# MCUReset.net
KiCad netlist of a schematic drawn in Altium Designer
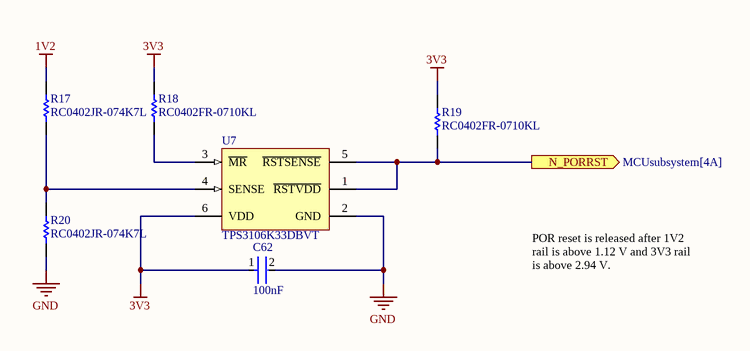
[diagram p0: MCUReset.SchDoc]

(export (version "E")
  (design (tool "Eeschema 10.0.6"))
  (components
    (comp (ref "C62")
      (value "GRM155R71E104KE14J")
      (footprint "FP-GRM155-0_05-IPC_C")
      (description "Chip Multilayer Ceramic Capacitors for General Purpose, 0402, 0.10uF, X7R, 15%, 10%, 25V")
      (fields (field (name "CAPACITANCE") "100nF") (field (name "TOLERANCE") "10%"))
      (libsource (lib "Altium Content Vault") (part "02cd4be3c70576c341d710602a673aa"))
    )
    (comp (ref "R17")
      (value "RC0402JR-074K7L")
      (footprint "RESC1005X40X25LL05T10")
      (fields (field (name "MANUFACTURER") "Yageo / Phycomp"))
      (libsource (lib "Altium Content Vault") (part "RES"))
    )
    (comp (ref "R18")
      (value "RC0402FR-0710KL")
      (footprint "RESC1005X40X25LL05T10")
      (fields (field (name "MANUFACTURER") "Yageo / Phycomp"))
      (libsource (lib "Altium Content Vault") (part "RES"))
    )
    (comp (ref "R19")
      (value "RC0402FR-0710KL")
      (footprint "RESC1005X40X25LL05T10")
      (fields (field (name "MANUFACTURER") "Yageo / Phycomp"))
      (libsource (lib "Altium Content Vault") (part "RES"))
    )
    (comp (ref "R20")
      (value "RC0402JR-074K7L")
      (footprint "RESC1005X40X25LL05T10")
      (fields (field (name "MANUFACTURER") "Yageo / Phycomp"))
      (libsource (lib "Altium Content Vault") (part "RES"))
    )
    (comp (ref "U7")
      (value "TPS3106K33DBVT")
      (footprint "DBV0006A_N")
      (fields (field (name "MANUFACTURER") "Texas Instruments"))
      (libsource (lib "Altium Content Vault") (part "TI-TPS3106K33DBV6"))
    )
  )
  (nets
    (net (code "1") (name "/N_PORRST") (class "Default")
      (node (ref "R19") (pin "1") (pinfunction "1_1") (pintype "passive"))
      (node (ref "U7") (pin "1") (pinfunction "~{RSTVDD}_1") (pintype "open_collector"))
      (node (ref "U7") (pin "5") (pinfunction "~{RSTSENSE}_5") (pintype "open_collector"))
    )
    (net (code "2") (name "1V2") (class "Default")
      (node (ref "R17") (pin "2") (pinfunction "2_2") (pintype "passive"))
    )
    (net (code "3") (name "3V3") (class "Default")
      (node (ref "C62") (pin "1") (pinfunction "1_1") (pintype "passive"))
      (node (ref "R18") (pin "2") (pinfunction "2_2") (pintype "passive"))
      (node (ref "R19") (pin "2") (pinfunction "2_2") (pintype "passive"))
      (node (ref "U7") (pin "6") (pinfunction "VDD_6") (pintype "power_in"))
    )
    (net (code "4") (name "GND") (class "Default")
      (node (ref "C62") (pin "2") (pinfunction "2_2") (pintype "passive"))
      (node (ref "R20") (pin "1") (pinfunction "1_1") (pintype "passive"))
      (node (ref "U7") (pin "2") (pinfunction "GND_2") (pintype "power_in"))
    )
    (net (code "5") (name "Net-(U7-SENSE)") (class "Default")
      (node (ref "R17") (pin "1") (pinfunction "1_1") (pintype "passive"))
      (node (ref "R20") (pin "2") (pinfunction "2_2") (pintype "passive"))
      (node (ref "U7") (pin "4") (pinfunction "SENSE_4") (pintype "input"))
    )
    (net (code "6") (name "Net-(U7-~{MR})") (class "Default")
      (node (ref "R18") (pin "1") (pinfunction "1_1") (pintype "passive"))
      (node (ref "U7") (pin "3") (pinfunction "~{MR}_3") (pintype "input"))
    )
  )
)
